# AJH_ss12144_v1_01.net
KiCad netlist of a schematic drawn in EAGLE
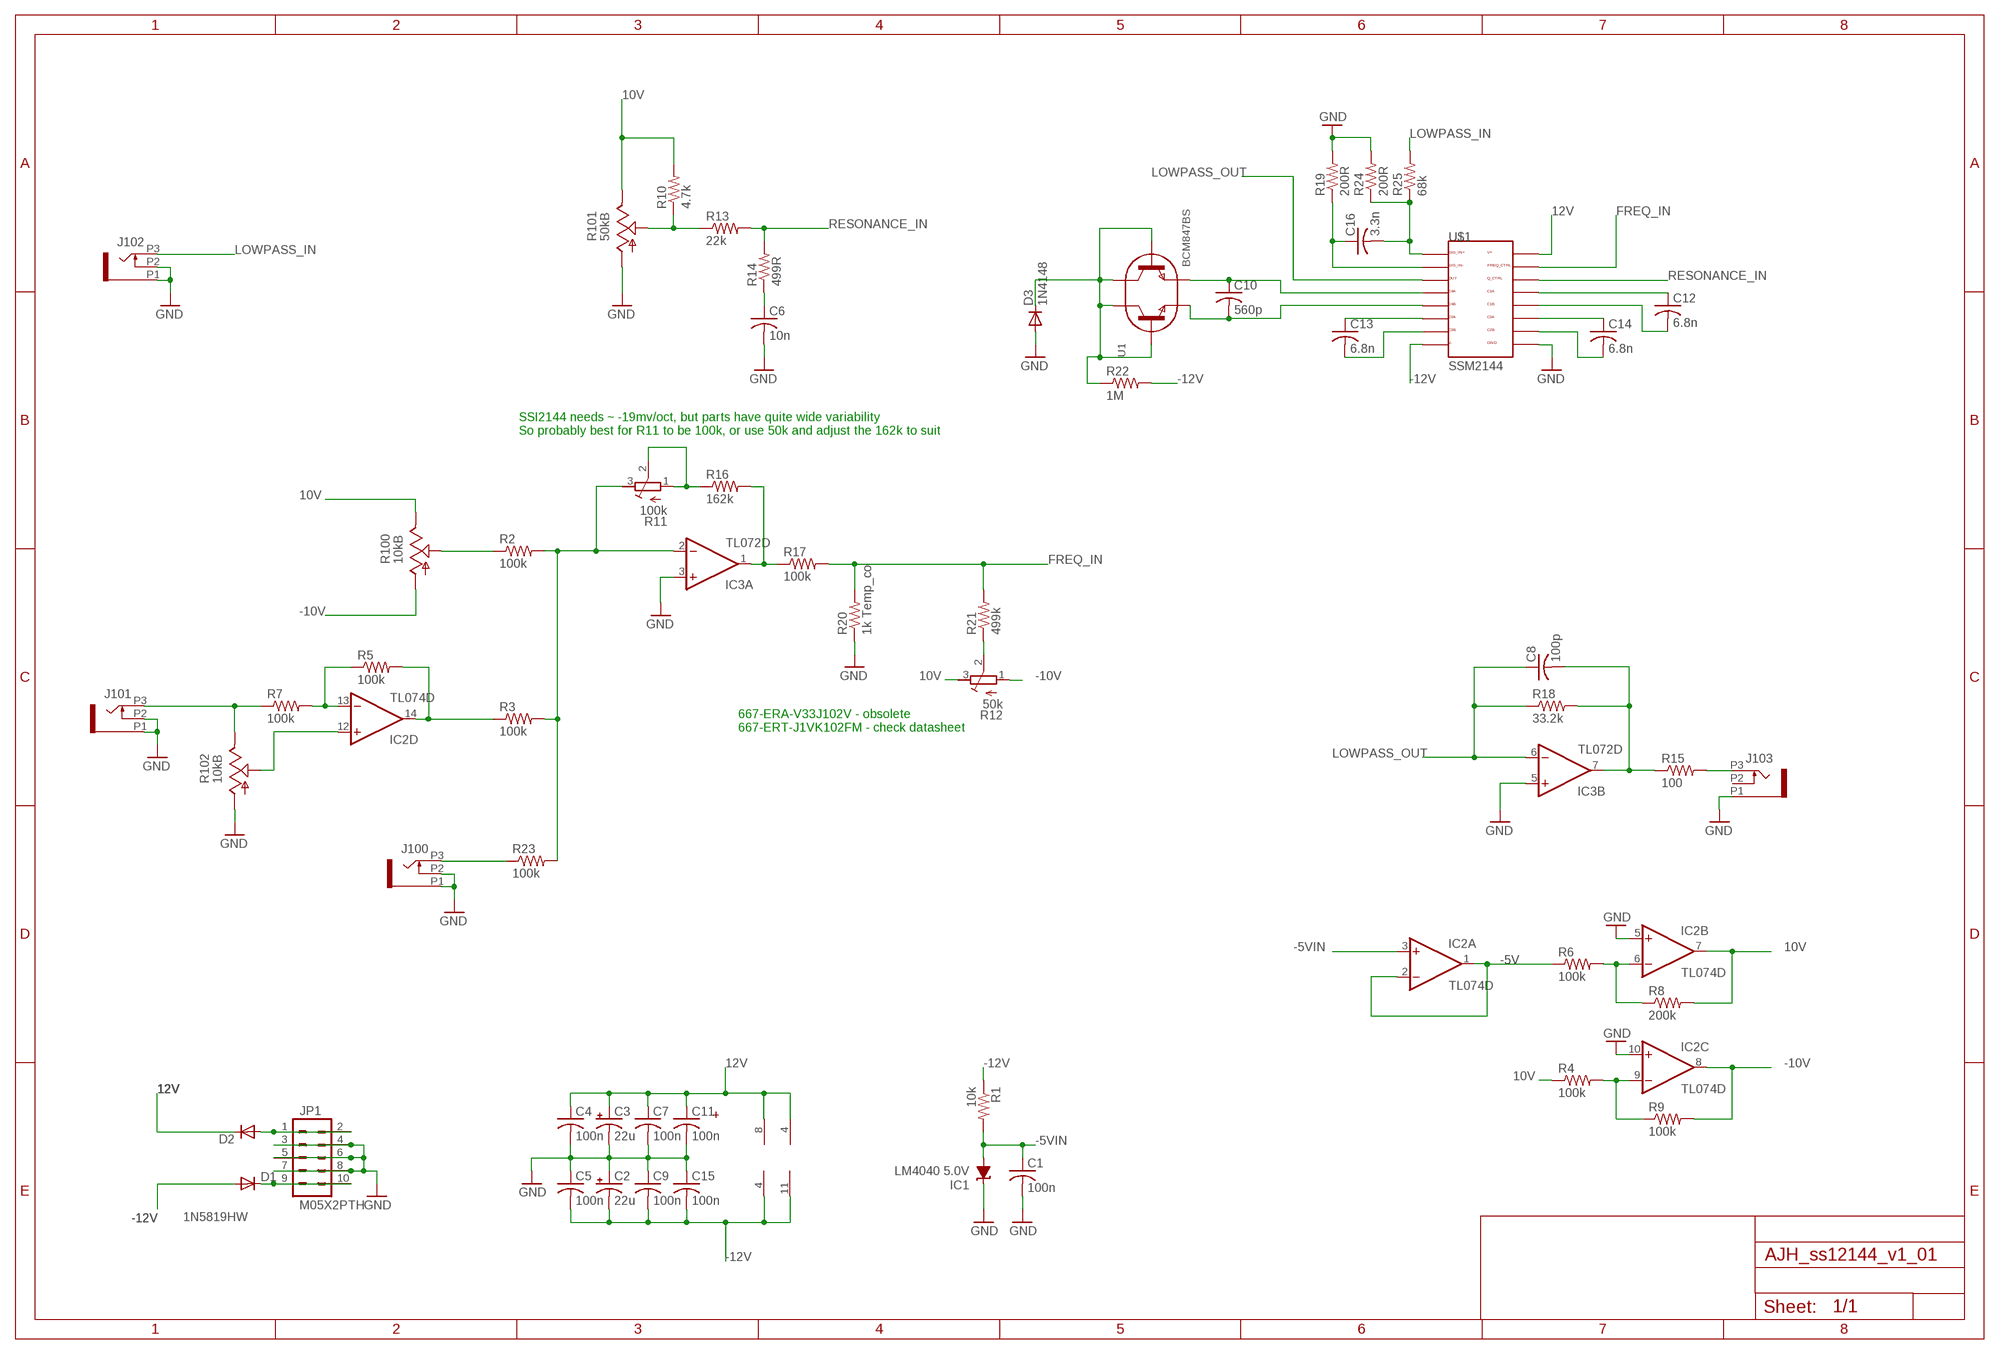
[diagram p0: schematic, sheet 1]

(export (version "E")
  (design (tool "Eeschema 10.0.6"))
  (components
    (comp (ref "C1")
      (value "100n")
      (footprint "eagle-import:C0603")
      (libsource (lib "eagle-import") (part "C-USC0603"))
    )
    (comp (ref "C2")
      (value "22u")
      (footprint "eagle-import:PANASONIC_B")
      (libsource (lib "eagle-import") (part "CPOL-USB"))
    )
    (comp (ref "C3")
      (value "22u")
      (footprint "eagle-import:PANASONIC_B")
      (libsource (lib "eagle-import") (part "CPOL-USB"))
    )
    (comp (ref "C4")
      (value "100n")
      (footprint "eagle-import:C0603")
      (libsource (lib "eagle-import") (part "C-USC0603"))
    )
    (comp (ref "C5")
      (value "100n")
      (footprint "eagle-import:C0603")
      (libsource (lib "eagle-import") (part "C-USC0603"))
    )
    (comp (ref "C6")
      (value "10n")
      (footprint "eagle-import:C0603")
      (libsource (lib "eagle-import") (part "C-USC0603"))
    )
    (comp (ref "C7")
      (value "100n")
      (footprint "eagle-import:C0603")
      (libsource (lib "eagle-import") (part "C-USC0603"))
    )
    (comp (ref "C8")
      (value "100p")
      (footprint "eagle-import:C0603")
      (libsource (lib "eagle-import") (part "C-USC0603"))
    )
    (comp (ref "C9")
      (value "100n")
      (footprint "eagle-import:C0603")
      (libsource (lib "eagle-import") (part "C-USC0603"))
    )
    (comp (ref "C10")
      (value "560p")
      (footprint "eagle-import:C0603")
      (libsource (lib "eagle-import") (part "C-USC0603"))
    )
    (comp (ref "C11")
      (value "100n")
      (footprint "eagle-import:C0603")
      (libsource (lib "eagle-import") (part "C-USC0603"))
    )
    (comp (ref "C12")
      (value "6.8n")
      (footprint "eagle-import:C0603")
      (libsource (lib "eagle-import") (part "C-USC0603"))
    )
    (comp (ref "C13")
      (value "6.8n")
      (footprint "eagle-import:C0603")
      (libsource (lib "eagle-import") (part "C-USC0603"))
    )
    (comp (ref "C14")
      (value "6.8n")
      (footprint "eagle-import:C0603")
      (libsource (lib "eagle-import") (part "C-USC0603"))
    )
    (comp (ref "C15")
      (value "100n")
      (footprint "eagle-import:C0603")
      (libsource (lib "eagle-import") (part "C-USC0603"))
    )
    (comp (ref "C16")
      (value "3.3n")
      (footprint "eagle-import:C0603")
      (libsource (lib "eagle-import") (part "C-USC0603"))
    )
    (comp (ref "D1")
      (value "1N5819HW")
      (footprint "eagle-import:SOD123")
      (libsource (lib "eagle-import") (part "DIODE-SOD123"))
    )
    (comp (ref "D2")
      (value "1N5819HW")
      (footprint "eagle-import:SOD123")
      (libsource (lib "eagle-import") (part "DIODE-SOD123"))
    )
    (comp (ref "D3")
      (value "1N4148")
      (footprint "eagle-import:SOD523")
      (libsource (lib "eagle-import") (part "DIODE-SOD523"))
    )
    (comp (ref "IC1")
      (value "LM4040 5.0V")
      (footprint "eagle-import:DBZ_R-PDSO-G3")
      (libsource (lib "eagle-import") (part "LM4041DBZC12"))
    )
    (comp (ref "IC2")
      (value "TL074D")
      (footprint "eagle-import:SO14")
      (libsource (lib "eagle-import") (part "TL074D"))
    )
    (comp (ref "IC3")
      (value "TL072D")
      (footprint "eagle-import:SO08")
      (libsource (lib "eagle-import") (part "TL072D"))
    )
    (comp (ref "J100")
      (value "PJ301_THONKICONN6")
      (footprint "eagle-import:WQP_PJ_301M6")
      (libsource (lib "eagle-import") (part "PJ301_THONKICONN6"))
    )
    (comp (ref "J101")
      (value "PJ301_THONKICONN6")
      (footprint "eagle-import:WQP_PJ_301M6")
      (libsource (lib "eagle-import") (part "PJ301_THONKICONN6"))
    )
    (comp (ref "J102")
      (value "PJ301_THONKICONN6")
      (footprint "eagle-import:WQP_PJ_301M6")
      (libsource (lib "eagle-import") (part "PJ301_THONKICONN6"))
    )
    (comp (ref "J103")
      (value "PJ301_THONKICONN6")
      (footprint "eagle-import:WQP_PJ_301M6")
      (libsource (lib "eagle-import") (part "PJ301_THONKICONN6"))
    )
    (comp (ref "JP1")
      (value "M05X2PTH")
      (footprint "eagle-import:AVR_ICSP")
      (libsource (lib "eagle-import") (part "M05X2PTH"))
    )
    (comp (ref "R1")
      (value "10k")
      (footprint "eagle-import:R0603")
      (libsource (lib "eagle-import") (part "R-US_R0603"))
    )
    (comp (ref "R2")
      (value "100k")
      (footprint "eagle-import:R0603")
      (libsource (lib "eagle-import") (part "R-US_R0603"))
    )
    (comp (ref "R3")
      (value "100k")
      (footprint "eagle-import:R0603")
      (libsource (lib "eagle-import") (part "R-US_R0603"))
    )
    (comp (ref "R4")
      (value "100k")
      (footprint "eagle-import:R0603")
      (libsource (lib "eagle-import") (part "R-US_R0603"))
    )
    (comp (ref "R5")
      (value "100k")
      (footprint "eagle-import:R0603")
      (libsource (lib "eagle-import") (part "R-US_R0603"))
    )
    (comp (ref "R6")
      (value "100k")
      (footprint "eagle-import:R0603")
      (libsource (lib "eagle-import") (part "R-US_R0603"))
    )
    (comp (ref "R7")
      (value "100k")
      (footprint "eagle-import:R0603")
      (libsource (lib "eagle-import") (part "R-US_R0603"))
    )
    (comp (ref "R8")
      (value "200k")
      (footprint "eagle-import:R0603")
      (libsource (lib "eagle-import") (part "R-US_R0603"))
    )
    (comp (ref "R9")
      (value "100k")
      (footprint "eagle-import:R0603")
      (libsource (lib "eagle-import") (part "R-US_R0603"))
    )
    (comp (ref "R10")
      (value "4.7k")
      (footprint "eagle-import:R0603")
      (libsource (lib "eagle-import") (part "R-US_R0603"))
    )
    (comp (ref "R11")
      (value "100k")
      (footprint "eagle-import:RTRIM3296X")
      (libsource (lib "eagle-import") (part "R-TRIMM3296X"))
    )
    (comp (ref "R12")
      (value "50k")
      (footprint "eagle-import:RTRIM3296X")
      (libsource (lib "eagle-import") (part "R-TRIMM3296X"))
    )
    (comp (ref "R13")
      (value "22k")
      (footprint "eagle-import:R0603")
      (libsource (lib "eagle-import") (part "R-US_R0603"))
    )
    (comp (ref "R14")
      (value "499R")
      (footprint "eagle-import:R0603")
      (libsource (lib "eagle-import") (part "R-US_R0603"))
    )
    (comp (ref "R15")
      (value "100")
      (footprint "eagle-import:R0603")
      (libsource (lib "eagle-import") (part "R-US_R0603"))
    )
    (comp (ref "R16")
      (value "162k")
      (footprint "eagle-import:R0603")
      (libsource (lib "eagle-import") (part "R-US_R0603"))
    )
    (comp (ref "R17")
      (value "100k")
      (footprint "eagle-import:R0603")
      (libsource (lib "eagle-import") (part "R-US_R0603"))
    )
    (comp (ref "R18")
      (value "33.2k")
      (footprint "eagle-import:R0603")
      (libsource (lib "eagle-import") (part "R-US_R0603"))
    )
    (comp (ref "R19")
      (value "200R")
      (footprint "eagle-import:R0603")
      (libsource (lib "eagle-import") (part "R-US_R0603"))
    )
    (comp (ref "R20")
      (value "1k Temp_co")
      (footprint "eagle-import:R0603")
      (libsource (lib "eagle-import") (part "R-US_R0603"))
    )
    (comp (ref "R21")
      (value "499k")
      (footprint "eagle-import:R0603")
      (libsource (lib "eagle-import") (part "R-US_R0603"))
    )
    (comp (ref "R22")
      (value "1M")
      (footprint "eagle-import:R0603")
      (libsource (lib "eagle-import") (part "R-US_R0603"))
    )
    (comp (ref "R23")
      (value "100k")
      (footprint "eagle-import:R0603")
      (libsource (lib "eagle-import") (part "R-US_R0603"))
    )
    (comp (ref "R24")
      (value "200R")
      (footprint "eagle-import:R0603")
      (libsource (lib "eagle-import") (part "R-US_R0603"))
    )
    (comp (ref "R25")
      (value "68k")
      (footprint "eagle-import:R0603")
      (libsource (lib "eagle-import") (part "R-US_R0603"))
    )
    (comp (ref "R100")
      (value "10kB")
      (footprint "eagle-import:ALPS_POT_VERTICAL")
      (libsource (lib "eagle-import") (part "POT_USVERTICAL"))
    )
    (comp (ref "R101")
      (value "50kB")
      (footprint "eagle-import:ALPS_POT_VERTICAL")
      (libsource (lib "eagle-import") (part "POT_USVERTICAL"))
    )
    (comp (ref "R102")
      (value "10kB")
      (footprint "eagle-import:ALPS_POT_VERTICAL")
      (libsource (lib "eagle-import") (part "POT_USVERTICAL"))
    )
    (comp (ref "U$1")
      (value "SSM2144")
      (footprint "eagle-import:SSOP16")
      (libsource (lib "eagle-import") (part "SSM2144"))
    )
    (comp (ref "U1")
      (value "BCM847BS")
      (footprint "eagle-import:SOT363")
      (libsource (lib "eagle-import") (part "BCM847BS"))
    )
  )
  (nets
    (net (code "1") (name "/-5V") (class "Default")
      (node (ref "IC2") (pin "1") (pinfunction "OUT_1") (pintype "output"))
      (node (ref "IC2") (pin "2") (pinfunction "-IN_2") (pintype "input"))
      (node (ref "R6") (pin "1") (pinfunction "1_1") (pintype "passive"))
    )
    (net (code "2") (name "/-5VIN") (class "Default")
      (node (ref "C1") (pin "1") (pinfunction "1_1") (pintype "passive"))
      (node (ref "IC1") (pin "2") (pinfunction "A_2") (pintype "passive"))
      (node (ref "IC2") (pin "3") (pinfunction "+IN_3") (pintype "input"))
      (node (ref "R1") (pin "2") (pinfunction "2_2") (pintype "passive"))
    )
    (net (code "3") (name "/-10V") (class "Default")
      (node (ref "IC2") (pin "8") (pinfunction "OUT_8") (pintype "output"))
      (node (ref "R100") (pin "P$3") (pinfunction "A_P$3") (pintype "passive"))
      (node (ref "R12") (pin "1") (pinfunction "E_1") (pintype "passive"))
      (node (ref "R9") (pin "2") (pinfunction "2_2") (pintype "passive"))
    )
    (net (code "4") (name "/-12V") (class "Default")
      (node (ref "C15") (pin "2") (pinfunction "2_2") (pintype "passive"))
      (node (ref "C2") (pin "-") (pinfunction "-_-") (pintype "passive"))
      (node (ref "C5") (pin "2") (pinfunction "2_2") (pintype "passive"))
      (node (ref "C9") (pin "2") (pinfunction "2_2") (pintype "passive"))
      (node (ref "D1") (pin "A") (pinfunction "A_A") (pintype "passive"))
      (node (ref "IC2") (pin "11") (pinfunction "V-_11") (pintype "power_in"))
      (node (ref "IC3") (pin "4") (pinfunction "V-_4") (pintype "power_in"))
      (node (ref "R1") (pin "1") (pinfunction "1_1") (pintype "passive"))
      (node (ref "R22") (pin "2") (pinfunction "2_2") (pintype "passive"))
      (node (ref "U$1") (pin "8") (pinfunction "V-_8") (pintype "bidirectional"))
    )
    (net (code "5") (name "/10V") (class "Default")
      (node (ref "IC2") (pin "7") (pinfunction "OUT_7") (pintype "output"))
      (node (ref "R10") (pin "2") (pinfunction "2_2") (pintype "passive"))
      (node (ref "R100") (pin "P$1") (pinfunction "E_P$1") (pintype "passive"))
      (node (ref "R101") (pin "P$1") (pinfunction "E_P$1") (pintype "passive"))
      (node (ref "R12") (pin "3") (pinfunction "A_3") (pintype "passive"))
      (node (ref "R4") (pin "1") (pinfunction "1_1") (pintype "passive"))
      (node (ref "R8") (pin "2") (pinfunction "2_2") (pintype "passive"))
    )
    (net (code "6") (name "/12V") (class "Default")
      (node (ref "C11") (pin "1") (pinfunction "1_1") (pintype "passive"))
      (node (ref "C3") (pin "+") (pinfunction "+_+") (pintype "passive"))
      (node (ref "C4") (pin "1") (pinfunction "1_1") (pintype "passive"))
      (node (ref "C7") (pin "1") (pinfunction "1_1") (pintype "passive"))
      (node (ref "D2") (pin "C") (pinfunction "C_C") (pintype "passive"))
      (node (ref "IC2") (pin "4") (pinfunction "V+_4") (pintype "power_in"))
      (node (ref "IC3") (pin "8") (pinfunction "V+_8") (pintype "power_in"))
      (node (ref "U$1") (pin "16") (pinfunction "V+_16") (pintype "bidirectional"))
    )
    (net (code "7") (name "/FREQ_IN") (class "Default")
      (node (ref "R17") (pin "2") (pinfunction "2_2") (pintype "passive"))
      (node (ref "R20") (pin "2") (pinfunction "2_2") (pintype "passive"))
      (node (ref "R21") (pin "2") (pinfunction "2_2") (pintype "passive"))
      (node (ref "U$1") (pin "15") (pinfunction "FREQ_CTRL_15") (pintype "bidirectional"))
    )
    (net (code "8") (name "/LOWPASS_IN") (class "Default")
      (node (ref "J102") (pin "P3") (pinfunction "3_P3") (pintype "passive"))
      (node (ref "R25") (pin "2") (pinfunction "2_2") (pintype "passive"))
    )
    (net (code "9") (name "/LOWPASS_OUT") (class "Default")
      (node (ref "C8") (pin "1") (pinfunction "1_1") (pintype "passive"))
      (node (ref "IC3") (pin "6") (pinfunction "-IN_6") (pintype "input"))
      (node (ref "R18") (pin "1") (pinfunction "1_1") (pintype "passive"))
      (node (ref "U$1") (pin "3") (pinfunction "OUT_3") (pintype "bidirectional"))
    )
    (net (code "10") (name "/RESONANCE_IN") (class "Default")
      (node (ref "R13") (pin "2") (pinfunction "2_2") (pintype "passive"))
      (node (ref "R14") (pin "2") (pinfunction "2_2") (pintype "passive"))
      (node (ref "U$1") (pin "14") (pinfunction "Q_CTRL_14") (pintype "bidirectional"))
    )
    (net (code "11") (name "GND") (class "Default")
      (node (ref "C1") (pin "2") (pinfunction "2_2") (pintype "passive"))
      (node (ref "C11") (pin "2") (pinfunction "2_2") (pintype "passive"))
      (node (ref "C15") (pin "1") (pinfunction "1_1") (pintype "passive"))
      (node (ref "C2") (pin "+") (pinfunction "+_+") (pintype "passive"))
      (node (ref "C3") (pin "-") (pinfunction "-_-") (pintype "passive"))
      (node (ref "C4") (pin "2") (pinfunction "2_2") (pintype "passive"))
      (node (ref "C5") (pin "1") (pinfunction "1_1") (pintype "passive"))
      (node (ref "C6") (pin "2") (pinfunction "2_2") (pintype "passive"))
      (node (ref "C7") (pin "2") (pinfunction "2_2") (pintype "passive"))
      (node (ref "C9") (pin "1") (pinfunction "1_1") (pintype "passive"))
      (node (ref "D3") (pin "A") (pinfunction "A_A") (pintype "passive"))
      (node (ref "IC1") (pin "1") (pinfunction "C_1") (pintype "passive"))
      (node (ref "IC2") (pin "10") (pinfunction "+IN_10") (pintype "input"))
      (node (ref "IC2") (pin "5") (pinfunction "+IN_5") (pintype "input"))
      (node (ref "IC3") (pin "3") (pinfunction "+IN_3") (pintype "input"))
      (node (ref "IC3") (pin "5") (pinfunction "+IN_5") (pintype "input"))
      (node (ref "J100") (pin "P1") (pinfunction "1_P1") (pintype "passive"))
      (node (ref "J100") (pin "P2") (pinfunction "2_P2") (pintype "passive"))
      (node (ref "J101") (pin "P1") (pinfunction "1_P1") (pintype "passive"))
      (node (ref "J101") (pin "P2") (pinfunction "2_P2") (pintype "passive"))
      (node (ref "J102") (pin "P1") (pinfunction "1_P1") (pintype "passive"))
      (node (ref "J102") (pin "P2") (pinfunction "2_P2") (pintype "passive"))
      (node (ref "J103") (pin "P1") (pinfunction "1_P1") (pintype "passive"))
      (node (ref "JP1") (pin "3") (pinfunction "3_3") (pintype "passive"))
      (node (ref "JP1") (pin "4") (pinfunction "4_4") (pintype "passive"))
      (node (ref "JP1") (pin "5") (pinfunction "5_5") (pintype "passive"))
      (node (ref "JP1") (pin "6") (pinfunction "6_6") (pintype "passive"))
      (node (ref "JP1") (pin "7") (pinfunction "7_7") (pintype "passive"))
      (node (ref "JP1") (pin "8") (pinfunction "8_8") (pintype "passive"))
      (node (ref "R101") (pin "P$3") (pinfunction "A_P$3") (pintype "passive"))
      (node (ref "R102") (pin "P$3") (pinfunction "A_P$3") (pintype "passive"))
      (node (ref "R19") (pin "2") (pinfunction "2_2") (pintype "passive"))
      (node (ref "R20") (pin "1") (pinfunction "1_1") (pintype "passive"))
      (node (ref "R24") (pin "2") (pinfunction "2_2") (pintype "passive"))
      (node (ref "U$1") (pin "9") (pinfunction "GND_9") (pintype "bidirectional"))
    )
    (net (code "12") (name "Net-(C6-Pad1)") (class "Default")
      (node (ref "C6") (pin "1") (pinfunction "1_1") (pintype "passive"))
      (node (ref "R14") (pin "1") (pinfunction "1_1") (pintype "passive"))
    )
    (net (code "13") (name "Net-(D1-PadC)") (class "Default")
      (node (ref "D1") (pin "C") (pinfunction "C_C") (pintype "passive"))
      (node (ref "JP1") (pin "10") (pinfunction "10_10") (pintype "passive"))
      (node (ref "JP1") (pin "9") (pinfunction "9_9") (pintype "passive"))
    )
    (net (code "14") (name "Net-(D2-PadA)") (class "Default")
      (node (ref "D2") (pin "A") (pinfunction "A_A") (pintype "passive"))
      (node (ref "JP1") (pin "1") (pinfunction "1_1") (pintype "passive"))
      (node (ref "JP1") (pin "2") (pinfunction "2_2") (pintype "passive"))
    )
    (net (code "15") (name "Net-(IC2B--IN)") (class "Default")
      (node (ref "IC2") (pin "6") (pinfunction "-IN_6") (pintype "input"))
      (node (ref "R6") (pin "2") (pinfunction "2_2") (pintype "passive"))
      (node (ref "R8") (pin "1") (pinfunction "1_1") (pintype "passive"))
    )
    (net (code "16") (name "Net-(IC2C--IN)") (class "Default")
      (node (ref "IC2") (pin "9") (pinfunction "-IN_9") (pintype "input"))
      (node (ref "R4") (pin "2") (pinfunction "2_2") (pintype "passive"))
      (node (ref "R9") (pin "1") (pinfunction "1_1") (pintype "passive"))
    )
    (net (code "17") (name "Net-(IC2D-+IN)") (class "Default")
      (node (ref "IC2") (pin "12") (pinfunction "+IN_12") (pintype "input"))
      (node (ref "R102") (pin "P$2") (pinfunction "S_P$2") (pintype "passive"))
    )
    (net (code "18") (name "Net-(IC2D--IN)") (class "Default")
      (node (ref "IC2") (pin "13") (pinfunction "-IN_13") (pintype "input"))
      (node (ref "R5") (pin "1") (pinfunction "1_1") (pintype "passive"))
      (node (ref "R7") (pin "2") (pinfunction "2_2") (pintype "passive"))
    )
    (net (code "19") (name "Net-(IC2D-OUT)") (class "Default")
      (node (ref "IC2") (pin "14") (pinfunction "OUT_14") (pintype "output"))
      (node (ref "R3") (pin "1") (pinfunction "1_1") (pintype "passive"))
      (node (ref "R5") (pin "2") (pinfunction "2_2") (pintype "passive"))
    )
    (net (code "20") (name "Net-(IC3A--IN)") (class "Default")
      (node (ref "IC3") (pin "2") (pinfunction "-IN_2") (pintype "input"))
      (node (ref "R11") (pin "3") (pinfunction "A_3") (pintype "passive"))
      (node (ref "R2") (pin "2") (pinfunction "2_2") (pintype "passive"))
      (node (ref "R23") (pin "2") (pinfunction "2_2") (pintype "passive"))
      (node (ref "R3") (pin "2") (pinfunction "2_2") (pintype "passive"))
    )
    (net (code "21") (name "Net-(IC3A-OUT)") (class "Default")
      (node (ref "IC3") (pin "1") (pinfunction "OUT_1") (pintype "output"))
      (node (ref "R16") (pin "2") (pinfunction "2_2") (pintype "passive"))
      (node (ref "R17") (pin "1") (pinfunction "1_1") (pintype "passive"))
    )
    (net (code "22") (name "Net-(IC3B-OUT)") (class "Default")
      (node (ref "C8") (pin "2") (pinfunction "2_2") (pintype "passive"))
      (node (ref "IC3") (pin "7") (pinfunction "OUT_7") (pintype "output"))
      (node (ref "R15") (pin "1") (pinfunction "1_1") (pintype "passive"))
      (node (ref "R18") (pin "2") (pinfunction "2_2") (pintype "passive"))
    )
    (net (code "23") (name "Net-(J100-3)") (class "Default")
      (node (ref "J100") (pin "P3") (pinfunction "3_P3") (pintype "passive"))
      (node (ref "R23") (pin "1") (pinfunction "1_1") (pintype "passive"))
    )
    (net (code "24") (name "Net-(J101-3)") (class "Default")
      (node (ref "J101") (pin "P3") (pinfunction "3_P3") (pintype "passive"))
      (node (ref "R102") (pin "P$1") (pinfunction "E_P$1") (pintype "passive"))
      (node (ref "R7") (pin "1") (pinfunction "1_1") (pintype "passive"))
    )
    (net (code "25") (name "Net-(J103-3)") (class "Default")
      (node (ref "J103") (pin "P3") (pinfunction "3_P3") (pintype "passive"))
      (node (ref "R15") (pin "2") (pinfunction "2_2") (pintype "passive"))
    )
    (net (code "26") (name "Net-(R11-E)") (class "Default")
      (node (ref "R11") (pin "1") (pinfunction "E_1") (pintype "passive"))
      (node (ref "R11") (pin "2") (pinfunction "S_2") (pintype "passive"))
      (node (ref "R16") (pin "1") (pinfunction "1_1") (pintype "passive"))
    )
    (net (code "27") (name "Net-(R12-S)") (class "Default")
      (node (ref "R12") (pin "2") (pinfunction "S_2") (pintype "passive"))
      (node (ref "R21") (pin "1") (pinfunction "1_1") (pintype "passive"))
    )
    (net (code "28") (name "Net-(R100-S)") (class "Default")
      (node (ref "R100") (pin "P$2") (pinfunction "S_P$2") (pintype "passive"))
      (node (ref "R2") (pin "1") (pinfunction "1_1") (pintype "passive"))
    )
    (net (code "29") (name "Net-(R101-S)") (class "Default")
      (node (ref "R10") (pin "1") (pinfunction "1_1") (pintype "passive"))
      (node (ref "R101") (pin "P$2") (pinfunction "S_P$2") (pintype "passive"))
      (node (ref "R13") (pin "1") (pinfunction "1_1") (pintype "passive"))
    )
    (net (code "30") (name "Net-(U$1-C1A)") (class "Default")
      (node (ref "C12") (pin "1") (pinfunction "1_1") (pintype "passive"))
      (node (ref "U$1") (pin "13") (pinfunction "C1A_13") (pintype "bidirectional"))
    )
    (net (code "31") (name "Net-(U$1-C1B)") (class "Default")
      (node (ref "C12") (pin "2") (pinfunction "2_2") (pintype "passive"))
      (node (ref "U$1") (pin "12") (pinfunction "C1B_12") (pintype "bidirectional"))
    )
    (net (code "32") (name "Net-(U$1-C2A)") (class "Default")
      (node (ref "C14") (pin "1") (pinfunction "1_1") (pintype "passive"))
      (node (ref "U$1") (pin "11") (pinfunction "C2A_11") (pintype "bidirectional"))
    )
    (net (code "33") (name "Net-(U$1-C2B)") (class "Default")
      (node (ref "C14") (pin "2") (pinfunction "2_2") (pintype "passive"))
      (node (ref "U$1") (pin "10") (pinfunction "C2B_10") (pintype "bidirectional"))
    )
    (net (code "34") (name "Net-(U$1-C3A)") (class "Default")
      (node (ref "C13") (pin "1") (pinfunction "1_1") (pintype "passive"))
      (node (ref "U$1") (pin "6") (pinfunction "C3A_6") (pintype "bidirectional"))
    )
    (net (code "35") (name "Net-(U$1-C3B)") (class "Default")
      (node (ref "C13") (pin "2") (pinfunction "2_2") (pintype "passive"))
      (node (ref "U$1") (pin "7") (pinfunction "C3B_7") (pintype "bidirectional"))
    )
    (net (code "36") (name "Net-(U$1-C4A)") (class "Default")
      (node (ref "C10") (pin "1") (pinfunction "1_1") (pintype "passive"))
      (node (ref "U$1") (pin "4") (pinfunction "C4A_4") (pintype "bidirectional"))
      (node (ref "U1") (pin "4") (pinfunction "E2_4") (pintype "passive"))
    )
    (net (code "37") (name "Net-(U$1-C4B)") (class "Default")
      (node (ref "C10") (pin "2") (pinfunction "2_2") (pintype "passive"))
      (node (ref "U$1") (pin "5") (pinfunction "C4B_5") (pintype "bidirectional"))
      (node (ref "U1") (pin "1") (pinfunction "E1_1") (pintype "passive"))
    )
    (net (code "38") (name "Net-(U$1-SIG_IN+)") (class "Default")
      (node (ref "C16") (pin "2") (pinfunction "2_2") (pintype "passive"))
      (node (ref "R24") (pin "1") (pinfunction "1_1") (pintype "passive"))
      (node (ref "R25") (pin "1") (pinfunction "1_1") (pintype "passive"))
      (node (ref "U$1") (pin "1") (pinfunction "SIG_IN+_1") (pintype "bidirectional"))
    )
    (net (code "39") (name "Net-(U$1-SIG_IN-)") (class "Default")
      (node (ref "C16") (pin "1") (pinfunction "1_1") (pintype "passive"))
      (node (ref "R19") (pin "1") (pinfunction "1_1") (pintype "passive"))
      (node (ref "U$1") (pin "2") (pinfunction "SIG_IN-_2") (pintype "bidirectional"))
    )
    (net (code "40") (name "Net-(U1-B1)") (class "Default")
      (node (ref "D3") (pin "C") (pinfunction "C_C") (pintype "passive"))
      (node (ref "R22") (pin "1") (pinfunction "1_1") (pintype "passive"))
      (node (ref "U1") (pin "2") (pinfunction "B1_2") (pintype "passive"))
      (node (ref "U1") (pin "3") (pinfunction "C2_3") (pintype "passive"))
      (node (ref "U1") (pin "5") (pinfunction "B2_5") (pintype "passive"))
      (node (ref "U1") (pin "6") (pinfunction "C1_6") (pintype "passive"))
    )
    (net (code "41") (name "unconnected-(J103-2-PadP2)") (class "Default")
      (node (ref "J103") (pin "P2") (pinfunction "2_P2") (pintype "passive"))
    )
  )
)
